# I2C_Modules.net
KiCad netlist of a schematic drawn in Altium Designer
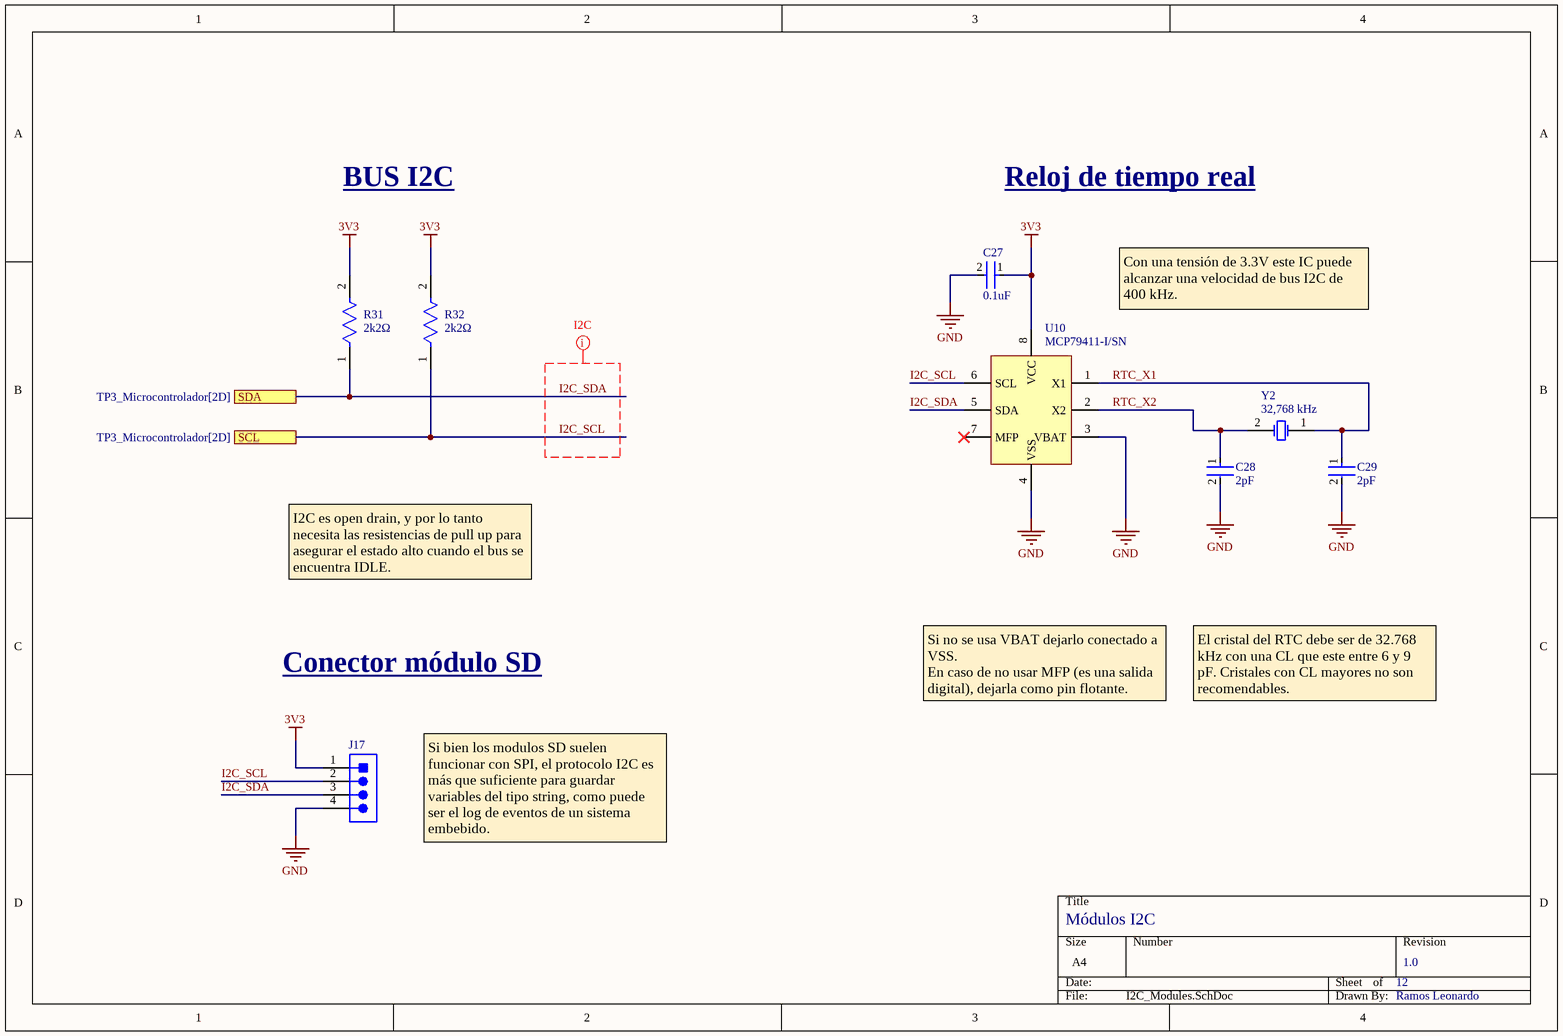
[diagram p0: I2C_Modules.SchDoc]

(export (version "E")
  (design (tool "Eeschema 10.0.6"))
  (components
    (comp (ref "C27")
      (value "0.1uF")
      (footprint "FP-CC0805-0_85-MFG")
      (description "CAP CER 0.1UF 25V X7R 0805")
      (fields (field (name "MANUFACTURER PART NUMBER") "CC0805KRX7R8BB104") (field (name "TOLERANCE") "0.1"))
      (libsource (lib "Altium Content Vault") (part "11868f565c42a9108669ba33697ecf6"))
    )
    (comp (ref "C28")
      (value "2pF")
      (footprint "FP-CC0805-0_85-MFG")
      (description "CAP CER 2pF 25V X7R 0805")
      (fields (field (name "MANUFACTURER PART NUMBER") "CC0805KRX7R8BB104") (field (name "TOLERANCE") "0.1"))
      (libsource (lib "Altium Content Vault") (part "11868f565c42a9108669ba33697ecf6"))
    )
    (comp (ref "C29")
      (value "2pF")
      (footprint "FP-CC0805-0_85-MFG")
      (description "CAP CER 2pF 25V X7R 0805")
      (fields (field (name "MANUFACTURER PART NUMBER") "CC0805KRX7R8BB104") (field (name "TOLERANCE") "0.1"))
      (libsource (lib "Altium Content Vault") (part "11868f565c42a9108669ba33697ecf6"))
    )
    (comp (ref "J17")
      (value "22-27-2041")
      (footprint "MOLX-22-27-2041_V")
      (description "Male Header, Pitch 2.54 mm, 1 x 4 Position, Height 11.7 mm, Tail Length 3.56 mm, RoHS, Bulk")
      (fields (field (name "MANUFACTURER") "Molex"))
      (libsource (lib "Altium Content Vault") (part "CN-1P-M-R4"))
    )
    (comp (ref "R31")
      (value "CRCW08054K70JNEA")
      (footprint "FP-CRCW0805-e3-IPC_B")
      (description "RES Thick Film, 5%, 0.125W, 200ppm/°C, 0805")
      (fields (field (name "TOLERANCE") "5%") (field (name "RESISTANCE") "2k2Ω"))
      (libsource (lib "Altium Content Vault") (part "1029c3af85768c4190bb7ad29bc67b5"))
    )
    (comp (ref "R32")
      (value "CRCW08054K70JNEA")
      (footprint "FP-CRCW0805-e3-IPC_B")
      (description "RES Thick Film, 5%, 0.125W, 200ppm/°C, 0805")
      (fields (field (name "TOLERANCE") "5%") (field (name "RESISTANCE") "2k2Ω"))
      (libsource (lib "Altium Content Vault") (part "1029c3af85768c4190bb7ad29bc67b5"))
    )
    (comp (ref "U10")
      (value "MCP79411-I/SN")
      (footprint "SOIC8-RTC")
      (description "Real time clock from Microchip")
      (libsource (lib "Componentes_custom") (part "MCP79411-I/SN"))
    )
    (comp (ref "Y2")
      (value "32,768 kHz")
      (footprint "WE-XTAL_CFPX-217")
      (description "830054236 WE-XTAL Quartz Crystal")
      (libsource (lib "Altium Content Vault") (part "WE-XTAL_CFPX-217"))
    )
  )
  (nets
    (net (code "1") (name "/I2C_SCL") (class "Default")
      (node (ref "J17") (pin "2") (pinfunction "2_2") (pintype "passive"))
      (node (ref "R32") (pin "1") (pinfunction "1_1") (pintype "passive"))
      (node (ref "U10") (pin "6") (pinfunction "SCL_6") (pintype "passive"))
    )
    (net (code "2") (name "/I2C_SDA") (class "Default")
      (node (ref "J17") (pin "3") (pinfunction "3_3") (pintype "passive"))
      (node (ref "R31") (pin "1") (pinfunction "1_1") (pintype "passive"))
      (node (ref "U10") (pin "5") (pinfunction "SDA_5") (pintype "passive"))
    )
    (net (code "3") (name "/RTC_X1") (class "Default")
      (node (ref "C29") (pin "1") (pinfunction "1_1") (pintype "passive"))
      (node (ref "U10") (pin "1") (pinfunction "X1_1") (pintype "passive"))
      (node (ref "Y2") (pin "1") (pinfunction "OSC1_1") (pintype "passive"))
    )
    (net (code "4") (name "/RTC_X2") (class "Default")
      (node (ref "C28") (pin "1") (pinfunction "1_1") (pintype "passive"))
      (node (ref "U10") (pin "2") (pinfunction "X2_2") (pintype "passive"))
      (node (ref "Y2") (pin "2") (pinfunction "OSC2_2") (pintype "passive"))
    )
    (net (code "5") (name "3V3") (class "Default")
      (node (ref "C27") (pin "1") (pinfunction "1_1") (pintype "passive"))
      (node (ref "J17") (pin "1") (pinfunction "1_1") (pintype "passive"))
      (node (ref "R31") (pin "2") (pinfunction "2_2") (pintype "passive"))
      (node (ref "R32") (pin "2") (pinfunction "2_2") (pintype "passive"))
      (node (ref "U10") (pin "8") (pinfunction "VCC_8") (pintype "passive"))
    )
    (net (code "6") (name "GND") (class "Default")
      (node (ref "C27") (pin "2") (pinfunction "2_2") (pintype "passive"))
      (node (ref "C28") (pin "2") (pinfunction "2_2") (pintype "passive"))
      (node (ref "C29") (pin "2") (pinfunction "2_2") (pintype "passive"))
      (node (ref "J17") (pin "4") (pinfunction "4_4") (pintype "passive"))
      (node (ref "U10") (pin "3") (pinfunction "VBAT_3") (pintype "passive"))
      (node (ref "U10") (pin "4") (pinfunction "VSS_4") (pintype "passive"))
    )
    (net (code "7") (name "unconnected-(U10-MFP-Pad7)") (class "Default")
      (node (ref "U10") (pin "7") (pinfunction "MFP_7") (pintype "passive+no_connect"))
    )
  )
)
